# main.net
KiCad netlist of a schematic drawn in Altium Designer
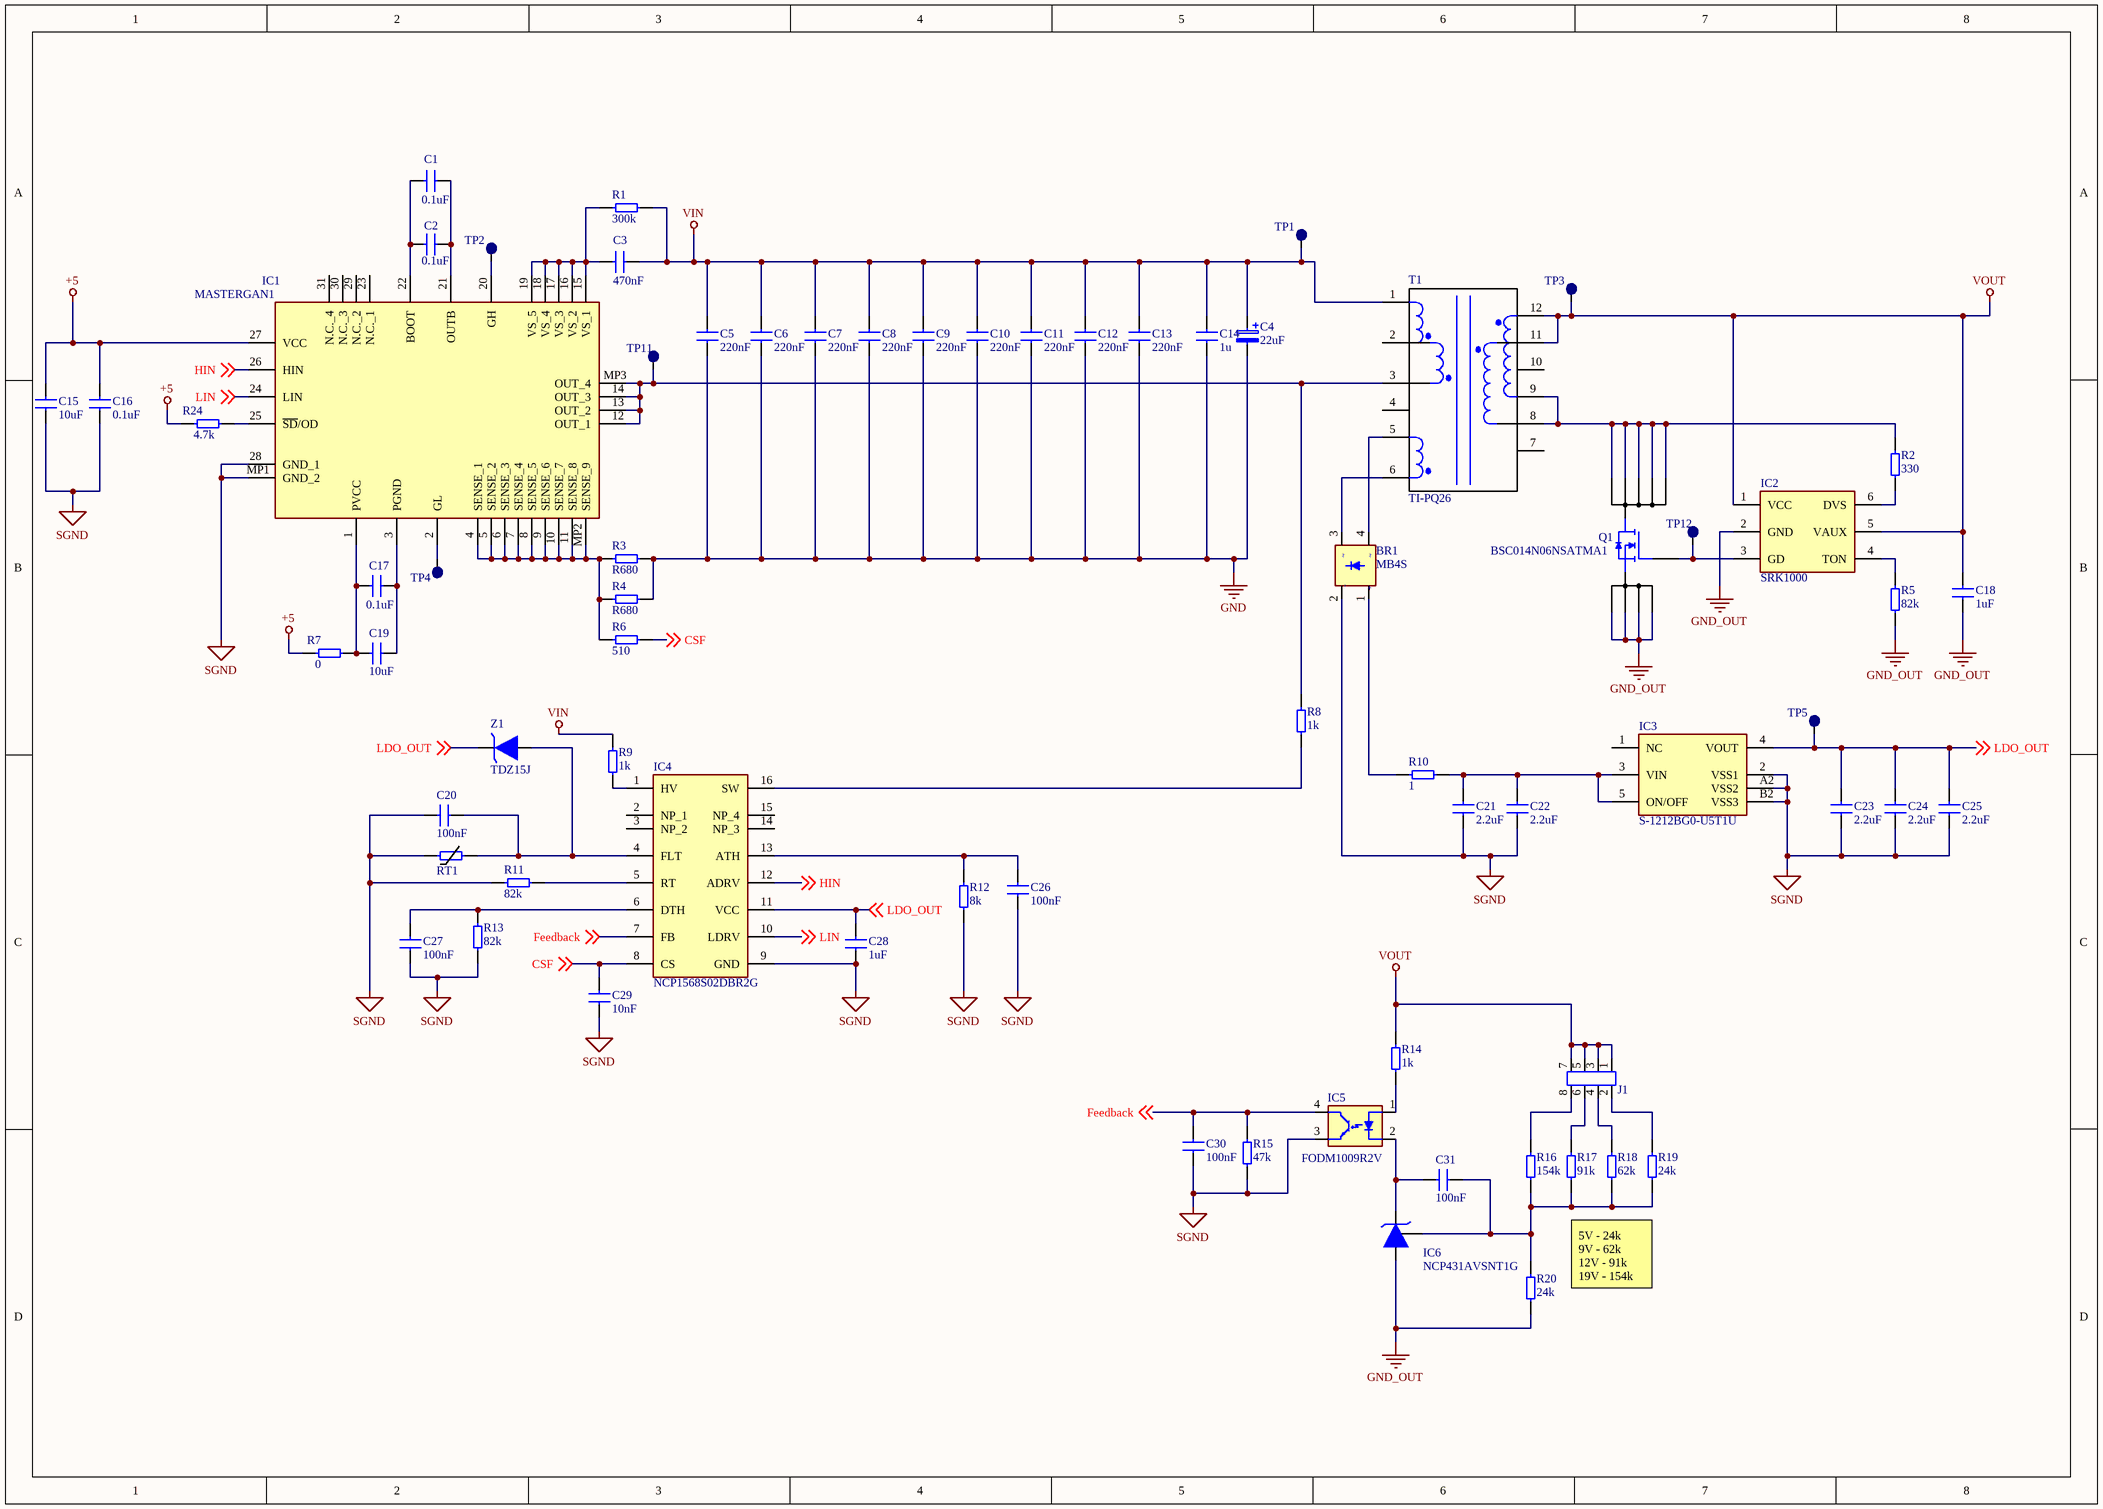
[diagram p0: main.SchDoc]

(export (version "E")
  (design (tool "Eeschema 10.0.6"))
  (components
    (comp (ref "BR1")
      (value "MB4S")
      (footprint "KN_ECART:SOP245P670X290-4N")
      (description "Bridge Rectifier")
      (fields (field (name "MOUSER PART NUMBER") "512-MB4S"))
      (libsource (lib "KN_ECART") (part "MB4S"))
    )
    (comp (ref "C1")
      (value "0.1uF")
      (footprint "KN_ECART:Capcitor_1206")
      (description "Capacitor - Standard SMD")
      (fields (field (name "VOLTAGE") "25V"))
      (libsource (lib "KN_ECART") (part "Capacitor_1206"))
    )
    (comp (ref "C2")
      (value "0.1uF")
      (footprint "KN_ECART:Capcitor_1206")
      (description "Capacitor - Standard SMD")
      (fields (field (name "VOLTAGE") "25V"))
      (libsource (lib "KN_ECART") (part "Capacitor_1206"))
    )
    (comp (ref "C3")
      (value "470nF")
      (footprint "KN_ECART:Capacitor_1812")
      (description "Capacitor - Standard SMD")
      (fields (field (name "VOLTAGE") "450V") (field (name "MPN") "CGA8N4X7T2W474K230KA"))
      (libsource (lib "") (part "Capacitor_1812_1"))
    )
    (comp (ref "C4")
      (value "22uF")
      (footprint "KN_ECART:CAPPRD500W60D1300H2700")
      (description "Capacitor - Electrolytic  THT")
      (fields (field (name "VOLTAGE") "500V") (field (name "MPN") "ESH226M500AL4AA"))
      (libsource (lib "KN_ECART") (part "Capacitor_Electrolytic_THT"))
    )
    (comp (ref "C5")
      (value "220nF")
      (footprint "KN_ECART:Capacitor_1812")
      (description "Capacitor - Standard SMD")
      (fields (field (name "VOLTAGE") "500") (field (name "MPN") "C1812C224MCRACTU"))
      (libsource (lib "") (part "Capacitor_1812_1"))
    )
    (comp (ref "C6")
      (value "220nF")
      (footprint "KN_ECART:Capacitor_1812")
      (description "Capacitor - Standard SMD")
      (fields (field (name "VOLTAGE") "500") (field (name "MPN") "C1812C224MCRACTU"))
      (libsource (lib "KN_ECART") (part "Capacitor_1812"))
    )
    (comp (ref "C7")
      (value "220nF")
      (footprint "KN_ECART:Capacitor_1812")
      (description "Capacitor - Standard SMD")
      (fields (field (name "VOLTAGE") "500") (field (name "MPN") "C1812C224MCRACTU"))
      (libsource (lib "") (part "Capacitor_1812_1"))
    )
    (comp (ref "C8")
      (value "220nF")
      (footprint "KN_ECART:Capacitor_1812")
      (description "Capacitor - Standard SMD")
      (fields (field (name "VOLTAGE") "500") (field (name "MPN") "C1812C224MCRACTU"))
      (libsource (lib "KN_ECART") (part "Capacitor_1812"))
    )
    (comp (ref "C9")
      (value "220nF")
      (footprint "KN_ECART:Capacitor_1812")
      (description "Capacitor - Standard SMD")
      (fields (field (name "VOLTAGE") "500") (field (name "MPN") "C1812C224MCRACTU"))
      (libsource (lib "") (part "Capacitor_1812_1"))
    )
    (comp (ref "C10")
      (value "220nF")
      (footprint "KN_ECART:Capacitor_1812")
      (description "Capacitor - Standard SMD")
      (fields (field (name "VOLTAGE") "500") (field (name "MPN") "C1812C224MCRACTU"))
      (libsource (lib "KN_ECART") (part "Capacitor_1812"))
    )
    (comp (ref "C11")
      (value "220nF")
      (footprint "KN_ECART:Capacitor_1812")
      (description "Capacitor - Standard SMD")
      (fields (field (name "VOLTAGE") "500") (field (name "MPN") "C1812C224MCRACTU"))
      (libsource (lib "KN_ECART") (part "Capacitor_1812"))
    )
    (comp (ref "C12")
      (value "220nF")
      (footprint "KN_ECART:Capacitor_1812")
      (description "Capacitor - Standard SMD")
      (fields (field (name "VOLTAGE") "500") (field (name "MPN") "C1812C224MCRACTU"))
      (libsource (lib "") (part "Capacitor_1812_1"))
    )
    (comp (ref "C13")
      (value "220nF")
      (footprint "KN_ECART:Capacitor_1812")
      (description "Capacitor - Standard SMD")
      (fields (field (name "VOLTAGE") "500") (field (name "MPN") "C1812C224MCRACTU"))
      (libsource (lib "KN_ECART") (part "Capacitor_1812"))
    )
    (comp (ref "C14")
      (value "1u")
      (footprint "TDKB58031")
      (description "Capacitor - Standard SMD")
      (fields (field (name "VOLTAGE") "450V") (field (name "MPN") "1206B104K451CT"))
      (libsource (lib "") (part "Capacitor_1206_2"))
    )
    (comp (ref "C15")
      (value "10uF")
      (footprint "KN_ECART:Capcitor_1206")
      (description "Capacitor - Standard SMD")
      (fields (field (name "VOLTAGE") "16V"))
      (libsource (lib "KN_ECART") (part "Capacitor_1206"))
    )
    (comp (ref "C16")
      (value "0.1uF")
      (footprint "KN_ECART:Capcitor_1206")
      (description "Capacitor - Standard SMD")
      (fields (field (name "VOLTAGE") "16V"))
      (libsource (lib "") (part "Capacitor_1206_1"))
    )
    (comp (ref "C17")
      (value "0.1uF")
      (footprint "KN_ECART:Capcitor_1206")
      (description "Capacitor - Standard SMD")
      (fields (field (name "VOLTAGE") "16V"))
      (libsource (lib "") (part "Capacitor_1206_1"))
    )
    (comp (ref "C18")
      (value "1uF")
      (footprint "KN_ECART:Capcitor_1206")
      (description "Capacitor - Standard SMD")
      (fields (field (name "VOLTAGE") "50") (field (name "MPN") "CL31B105KBHNFNE"))
      (libsource (lib "KN_ECART") (part "Capacitor_1206"))
    )
    (comp (ref "C19")
      (value "10uF")
      (footprint "KN_ECART:Capcitor_1206")
      (description "Capacitor - Standard SMD")
      (fields (field (name "VOLTAGE") "16V"))
      (libsource (lib "") (part "Capacitor_1206_1"))
    )
    (comp (ref "C20")
      (value "100nF")
      (footprint "KN_ECART:Capcitor_1206")
      (description "Capacitor - Standard SMD")
      (fields (field (name "VOLTAGE") "50V"))
      (libsource (lib "") (part "Capacitor_1206_1"))
    )
    (comp (ref "C21")
      (value "2.2uF")
      (footprint "KN_ECART:Capcitor_1206")
      (description "Capacitor - Standard SMD")
      (fields (field (name "VOLTAGE") "50V") (field (name "MPN") "CL31B225KBHNFNE"))
      (libsource (lib "") (part "Capacitor_1206_1"))
    )
    (comp (ref "C22")
      (value "2.2uF")
      (footprint "KN_ECART:Capcitor_1206")
      (description "Capacitor - Standard SMD")
      (fields (field (name "VOLTAGE") "50V") (field (name "MPN") "CL31B225KBHNFNE"))
      (libsource (lib "") (part "Capacitor_1206_1"))
    )
    (comp (ref "C23")
      (value "2.2uF")
      (footprint "KN_ECART:Capcitor_1206")
      (description "Capacitor - Standard SMD")
      (fields (field (name "VOLTAGE") "50V") (field (name "MPN") "CL31B225KBHNFNE"))
      (libsource (lib "") (part "Capacitor_1206_1"))
    )
    (comp (ref "C24")
      (value "2.2uF")
      (footprint "KN_ECART:Capcitor_1206")
      (description "Capacitor - Standard SMD")
      (fields (field (name "VOLTAGE") "50V") (field (name "MPN") "CL31B225KBHNFNE"))
      (libsource (lib "") (part "Capacitor_1206_1"))
    )
    (comp (ref "C25")
      (value "2.2uF")
      (footprint "KN_ECART:Capcitor_1206")
      (description "Capacitor - Standard SMD")
      (fields (field (name "VOLTAGE") "50V") (field (name "MPN") "CL31B225KBHNFNE"))
      (libsource (lib "") (part "Capacitor_1206_1"))
    )
    (comp (ref "C26")
      (value "100nF")
      (footprint "KN_ECART:Capcitor_1206")
      (description "Capacitor - Standard SMD")
      (fields (field (name "VOLTAGE") "50V"))
      (libsource (lib "") (part "Capacitor_1206_1"))
    )
    (comp (ref "C27")
      (value "100nF")
      (footprint "KN_ECART:Capcitor_1206")
      (description "Capacitor - Standard SMD")
      (fields (field (name "VOLTAGE") "50V"))
      (libsource (lib "KN_ECART") (part "Capacitor_1206"))
    )
    (comp (ref "C28")
      (value "1uF")
      (footprint "KN_ECART:Capacitor_0805")
      (description "Capacitor - Standard SMD")
      (fields (field (name "VOLTAGE") "25V"))
      (libsource (lib "KN_ECART") (part "Capacitor_0805"))
    )
    (comp (ref "C29")
      (value "10nF")
      (footprint "KN_ECART:Capcitor_1206")
      (description "Capacitor - Standard SMD")
      (fields (field (name "VOLTAGE") "50V"))
      (libsource (lib "KN_ECART") (part "Capacitor_1206"))
    )
    (comp (ref "C30")
      (value "100nF")
      (footprint "KN_ECART:Capcitor_1206")
      (description "Capacitor - Standard SMD")
      (fields (field (name "VOLTAGE") "50V"))
      (libsource (lib "") (part "Capacitor_1206_1"))
    )
    (comp (ref "C31")
      (value "100nF")
      (footprint "KN_ECART:Capcitor_1206")
      (description "Capacitor - Standard SMD")
      (fields (field (name "VOLTAGE") "50V"))
      (libsource (lib "KN_ECART") (part "Capacitor_1206"))
    )
    (comp (ref "IC1")
      (value "MASTERGAN1")
      (footprint "MASTERGAN1")
      (description "Integrated Circuit")
      (fields (field (name "MOUSER PART NUMBER") "511-MASTERGAN1"))
      (libsource (lib "KN_ECART") (part "MASTERGAN1"))
    )
    (comp (ref "IC2")
      (value "SRK1000")
      (footprint "KN_ECART:SOT95P280X145-6N")
      (description "Integrated Circuit")
      (fields (field (name "MOUSER PART NUMBER") "511-SRK1000"))
      (libsource (lib "KN_ECART") (part "SRK1000"))
    )
    (comp (ref "IC3")
      (value "S-1212BG0-U5T1U")
      (footprint "KN_ECART:S1212BG0U5T1U")
      (description "Integrated Circuit")
      (fields (field (name "MOUSER PART NUMBER") "628-S-1212BG0-U5T1U"))
      (libsource (lib "KN_ECART") (part "S-1212BG0-U5T1U"))
    )
    (comp (ref "IC4")
      (value "NCP1568S02DBR2G")
      (footprint "KN_ECART:SOIC127P600X175-16N")
      (description "Integrated Circuit")
      (fields (field (name "MOUSER PART NUMBER") "863-NCP1568S02DBR2G"))
      (libsource (lib "KN_ECART") (part "NCP1568S02DBR2G"))
    )
    (comp (ref "IC5")
      (value "FODM1009R2V")
      (footprint "KN_ECART:FODM1009R2V")
      (description "Integrated Circuit")
      (fields (field (name "MOUSER PART NUMBER") "863-FODM1009R2V"))
      (libsource (lib "KN_ECART") (part "FODM1009R2V"))
    )
    (comp (ref "IC6")
      (value "NCP431AVSNT1G")
      (footprint "SOT96P237X111-3N")
      (description "Programmable Precision\r\nReference")
      (fields (field (name "MOUSER PART NUMBER") "863-NCP431AVSNT1G"))
      (libsource (lib "KN_ECART") (part "NCP431AVSNT1G"))
    )
    (comp (ref "J1")
      (value "Header_2x4")
      (footprint "Header_2x4")
      (libsource (lib "KN_ECART") (part "Header_2x4"))
    )
    (comp (ref "Q1")
      (value "BSC014N06NSATMA1")
      (footprint "BSC010N04LS6ATMA1")
      (description "MOSFET (N-Channel)")
      (fields (field (name "MOUSER PART NUMBER") "726-BSC014N06NSATMA1"))
      (libsource (lib "KN_ECART") (part "BSC014N06NSATMA1"))
    )
    (comp (ref "R1")
      (value "300k")
      (footprint "KN_ECART:Resistor_1206")
      (description "Resistor - Standard SMD")
      (libsource (lib "KN_ECART") (part "Resistor_1206"))
    )
    (comp (ref "R2")
      (value "330")
      (footprint "KN_ECART:Resistor_1206")
      (description "Resistor - Standard SMD")
      (libsource (lib "KN_ECART") (part "Resistor_1206"))
    )
    (comp (ref "R3")
      (value "R680")
      (footprint "KN_ECART:Resistor_1206")
      (description "Resistor - Standard SMD")
      (fields (field (name "MPN") "PE1206FRF7W0R68L"))
      (libsource (lib "KN_ECART") (part "Resistor_1206"))
    )
    (comp (ref "R4")
      (value "R680")
      (footprint "KN_ECART:Resistor_1206")
      (description "Resistor - Standard SMD")
      (fields (field (name "MPN") "PE1206FRF7W0R68L"))
      (libsource (lib "KN_ECART") (part "Resistor_1206"))
    )
    (comp (ref "R5")
      (value "82k")
      (footprint "KN_ECART:Resistor_1206")
      (description "Resistor - Standard SMD")
      (libsource (lib "KN_ECART") (part "Resistor_1206"))
    )
    (comp (ref "R6")
      (value "510")
      (footprint "KN_ECART:Resistor_1206")
      (description "Resistor - Standard SMD")
      (libsource (lib "KN_ECART") (part "Resistor_1206"))
    )
    (comp (ref "R7")
      (value "0")
      (footprint "KN_ECART:Resistor_0805")
      (description "Resistor - Standard SMD")
      (libsource (lib "KN_ECART") (part "Resistor_0805"))
    )
    (comp (ref "R8")
      (value "1k")
      (footprint "KN_ECART:Resistor_1206")
      (description "Resistor - Standard SMD")
      (libsource (lib "KN_ECART") (part "Resistor_1206"))
    )
    (comp (ref "R9")
      (value "1k")
      (footprint "KN_ECART:Resistor_1206")
      (description "Resistor - Standard SMD")
      (libsource (lib "KN_ECART") (part "Resistor_1206"))
    )
    (comp (ref "R10")
      (value "1")
      (footprint "KN_ECART:Resistor_1206")
      (description "Resistor - Standard SMD")
      (libsource (lib "KN_ECART") (part "Resistor_1206"))
    )
    (comp (ref "R11")
      (value "82k")
      (footprint "KN_ECART:Resistor_1206")
      (description "Resistor - Standard SMD")
      (libsource (lib "KN_ECART") (part "Resistor_1206"))
    )
    (comp (ref "R12")
      (value "8k")
      (footprint "KN_ECART:Resistor_1206")
      (description "Resistor - Standard SMD")
      (libsource (lib "KN_ECART") (part "Resistor_1206"))
    )
    (comp (ref "R13")
      (value "82k")
      (footprint "KN_ECART:Resistor_1206")
      (description "Resistor - Standard SMD")
      (libsource (lib "KN_ECART") (part "Resistor_1206"))
    )
    (comp (ref "R14")
      (value "1k")
      (footprint "KN_ECART:Resistor_1206")
      (description "Resistor - Standard SMD")
      (libsource (lib "KN_ECART") (part "Resistor_1206"))
    )
    (comp (ref "R15")
      (value "47k")
      (footprint "KN_ECART:Resistor_1206")
      (description "Resistor - Standard SMD")
      (libsource (lib "KN_ECART") (part "Resistor_1206"))
    )
    (comp (ref "R16")
      (value "154k")
      (footprint "KN_ECART:Resistor_0805")
      (description "Resistor - Standard SMD")
      (libsource (lib "KN_ECART") (part "Resistor_0805"))
    )
    (comp (ref "R17")
      (value "91k")
      (footprint "KN_ECART:Resistor_0805")
      (description "Resistor - Standard SMD")
      (libsource (lib "KN_ECART") (part "Resistor_0805"))
    )
    (comp (ref "R18")
      (value "62k")
      (footprint "KN_ECART:Resistor_0805")
      (description "Resistor - Standard SMD")
      (libsource (lib "KN_ECART") (part "Resistor_0805"))
    )
    (comp (ref "R19")
      (value "24k")
      (footprint "KN_ECART:Resistor_0805")
      (description "Resistor - Standard SMD")
      (libsource (lib "KN_ECART") (part "Resistor_0805"))
    )
    (comp (ref "R20")
      (value "24k")
      (footprint "KN_ECART:Resistor_1206")
      (description "Resistor - Standard SMD")
      (libsource (lib "KN_ECART") (part "Resistor_1206"))
    )
    (comp (ref "R24")
      (value "4.7k")
      (footprint "KN_ECART:Resistor_0805")
      (description "Resistor - Standard SMD")
      (libsource (lib "KN_ECART") (part "Resistor_0805"))
    )
    (comp (ref "RT1")
      (value "NTCG104EF104FT1SX")
      (footprint "KN_ECART:THRMC1005X55N")
      (description "Thermistor")
      (fields (field (name "MOUSER PART NUMBER") "810-NTC104EF104FT1SX"))
      (libsource (lib "KN_ECART") (part "NTCG104EF104FT1SX"))
    )
    (comp (ref "T1")
      (value "TI-PQ26")
      (footprint "PQ26-20-K")
      (description "Transformer")
      (fields (field (name "MPN") "TI-PQ26/20-EPR11"))
      (libsource (lib "KN_ECART") (part "TI-PQ26"))
    )
    (comp (ref "TP1")
      (value "Test point")
      (footprint "Test point")
      (libsource (lib "KN_ECART") (part "Test point"))
    )
    (comp (ref "TP2")
      (value "Test point")
      (footprint "Test point")
      (libsource (lib "KN_ECART") (part "Test point"))
    )
    (comp (ref "TP3")
      (value "Test point")
      (footprint "Test point")
      (libsource (lib "KN_ECART") (part "Test point"))
    )
    (comp (ref "TP4")
      (value "Test point")
      (footprint "Test point")
      (libsource (lib "KN_ECART") (part "Test point"))
    )
    (comp (ref "TP5")
      (value "Test point")
      (footprint "Test point")
      (libsource (lib "KN_ECART") (part "Test point"))
    )
    (comp (ref "TP11")
      (value "Test point")
      (footprint "Test point")
      (libsource (lib "KN_ECART") (part "Test point"))
    )
    (comp (ref "TP12")
      (value "Test point")
      (footprint "Test point")
      (libsource (lib "KN_ECART") (part "Test point"))
    )
    (comp (ref "Z1")
      (value "TDZ15J")
      (footprint "KN_ECART:SODFL4725X105N")
      (description "Zener Diode")
      (fields (field (name "ARROW PART NUMBER") "TDZ3V3J,115"))
      (libsource (lib "KN_ECART") (part "TDZ15J"))
    )
  )
  (nets
    (net (code "1") (name "+5") (class "Default")
      (node (ref "C15") (pin "2") (pintype "passive"))
      (node (ref "C16") (pin "1") (pintype "passive"))
      (node (ref "IC1") (pin "27") (pinfunction "VCC_27") (pintype "passive"))
      (node (ref "R24") (pin "1") (pintype "passive"))
      (node (ref "R7") (pin "1") (pintype "passive"))
    )
    (net (code "2") (name "CSF") (class "Default")
      (node (ref "C29") (pin "1") (pintype "passive"))
      (node (ref "IC4") (pin "8") (pinfunction "CS_8") (pintype "passive"))
      (node (ref "R6") (pin "1") (pintype "passive"))
    )
    (net (code "3") (name "Feedback") (class "Default")
      (node (ref "C30") (pin "2") (pintype "passive"))
      (node (ref "IC4") (pin "7") (pinfunction "FB_7") (pintype "passive"))
      (node (ref "IC5") (pin "4") (pinfunction "C_4") (pintype "passive"))
      (node (ref "R15") (pin "2") (pintype "passive"))
    )
    (net (code "4") (name "GND") (class "Default")
      (node (ref "C10") (pin "2") (pintype "passive"))
      (node (ref "C11") (pin "2") (pintype "passive"))
      (node (ref "C12") (pin "1") (pintype "passive"))
      (node (ref "C13") (pin "2") (pintype "passive"))
      (node (ref "C14") (pin "2") (pintype "passive"))
      (node (ref "C4") (pin "2") (pintype "passive"))
      (node (ref "C5") (pin "1") (pintype "passive"))
      (node (ref "C6") (pin "2") (pintype "passive"))
      (node (ref "C7") (pin "1") (pintype "passive"))
      (node (ref "C8") (pin "2") (pintype "passive"))
      (node (ref "C9") (pin "1") (pintype "passive"))
      (node (ref "R3") (pin "2") (pintype "passive"))
      (node (ref "R4") (pin "2") (pintype "passive"))
    )
    (net (code "5") (name "GND_OUT") (class "Default")
      (node (ref "C18") (pin "1") (pintype "passive"))
      (node (ref "IC2") (pin "2") (pinfunction "GND_2") (pintype "passive"))
      (node (ref "IC6") (pin "3") (pinfunction "A_3") (pintype "passive"))
      (node (ref "Q1") (pin "1") (pinfunction "S_1_1") (pintype "passive"))
      (node (ref "Q1") (pin "10") (pinfunction "S_4_10") (pintype "passive"))
      (node (ref "Q1") (pin "2") (pinfunction "S_2_2") (pintype "passive"))
      (node (ref "Q1") (pin "3") (pinfunction "S_3_3") (pintype "passive"))
      (node (ref "R20") (pin "1") (pintype "passive"))
      (node (ref "R5") (pin "1") (pintype "passive"))
    )
    (net (code "6") (name "HIN") (class "Default")
      (node (ref "IC1") (pin "26") (pinfunction "HIN_26") (pintype "passive"))
      (node (ref "IC4") (pin "12") (pinfunction "ADRV_12") (pintype "passive"))
    )
    (net (code "7") (name "LDO_OUT") (class "Default")
      (node (ref "C23") (pin "2") (pintype "passive"))
      (node (ref "C24") (pin "2") (pintype "passive"))
      (node (ref "C25") (pin "2") (pintype "passive"))
      (node (ref "C28") (pin "2") (pintype "passive"))
      (node (ref "IC3") (pin "4") (pinfunction "VOUT_4") (pintype "passive"))
      (node (ref "IC4") (pin "11") (pinfunction "VCC_11") (pintype "passive"))
      (node (ref "TP5") (pin "1") (pintype "passive"))
      (node (ref "Z1") (pin "1") (pinfunction "K_1") (pintype "passive"))
    )
    (net (code "8") (name "LIN") (class "Default")
      (node (ref "IC1") (pin "24") (pinfunction "LIN_24") (pintype "passive"))
      (node (ref "IC4") (pin "10") (pinfunction "LDRV_10") (pintype "passive"))
    )
    (net (code "9") (name "Net-(BR1-Pad1)") (class "Default")
      (node (ref "BR1") (pin "1") (pintype "passive"))
      (node (ref "R10") (pin "1") (pintype "passive"))
    )
    (net (code "10") (name "Net-(BR1-Pad3)") (class "Default")
      (node (ref "BR1") (pin "3") (pintype "passive"))
      (node (ref "T1") (pin "6") (pintype "passive"))
    )
    (net (code "11") (name "Net-(BR1-Pad4)") (class "Default")
      (node (ref "BR1") (pin "4") (pintype "passive"))
      (node (ref "T1") (pin "5") (pintype "passive"))
    )
    (net (code "12") (name "Net-(IC1-BOOT)") (class "Default")
      (node (ref "C1") (pin "1") (pintype "passive"))
      (node (ref "C2") (pin "1") (pintype "passive"))
      (node (ref "IC1") (pin "22") (pinfunction "BOOT_22") (pintype "passive"))
    )
    (net (code "13") (name "Net-(IC1-GH)") (class "Default")
      (node (ref "IC1") (pin "20") (pinfunction "GH_20") (pintype "passive"))
      (node (ref "TP2") (pin "1") (pintype "passive"))
    )
    (net (code "14") (name "Net-(IC1-GL)") (class "Default")
      (node (ref "IC1") (pin "2") (pinfunction "GL_2") (pintype "passive"))
      (node (ref "TP4") (pin "1") (pintype "passive"))
    )
    (net (code "15") (name "Net-(IC1-OUTB)") (class "Default")
      (node (ref "C1") (pin "2") (pintype "passive"))
      (node (ref "C2") (pin "2") (pintype "passive"))
      (node (ref "IC1") (pin "21") (pinfunction "OUTB_21") (pintype "passive"))
    )
    (net (code "16") (name "Net-(IC1-OUT_1)") (class "Default")
      (node (ref "IC1") (pin "12") (pinfunction "OUT_1_12") (pintype "passive"))
      (node (ref "IC1") (pin "13") (pinfunction "OUT_2_13") (pintype "passive"))
      (node (ref "IC1") (pin "14") (pinfunction "OUT_3_14") (pintype "passive"))
      (node (ref "IC1") (pin "MP3") (pinfunction "OUT_4_MP3") (pintype "passive"))
      (node (ref "R8") (pin "2") (pintype "passive"))
      (node (ref "T1") (pin "3") (pintype "passive"))
      (node (ref "TP11") (pin "1") (pintype "passive"))
    )
    (net (code "17") (name "Net-(IC1-PGND)") (class "Default")
      (node (ref "C17") (pin "2") (pintype "passive"))
      (node (ref "C19") (pin "2") (pintype "passive"))
      (node (ref "IC1") (pin "3") (pinfunction "PGND_3") (pintype "passive"))
    )
    (net (code "18") (name "Net-(IC1-PVCC)") (class "Default")
      (node (ref "C17") (pin "1") (pintype "passive"))
      (node (ref "C19") (pin "1") (pintype "passive"))
      (node (ref "IC1") (pin "1") (pinfunction "PVCC_1") (pintype "passive"))
      (node (ref "R7") (pin "2") (pintype "passive"))
    )
    (net (code "19") (name "Net-(IC1-SENSE_1)") (class "Default")
      (node (ref "IC1") (pin "10") (pinfunction "SENSE_7_10") (pintype "passive"))
      (node (ref "IC1") (pin "11") (pinfunction "SENSE_8_11") (pintype "passive"))
      (node (ref "IC1") (pin "4") (pinfunction "SENSE_1_4") (pintype "passive"))
      (node (ref "IC1") (pin "5") (pinfunction "SENSE_2_5") (pintype "passive"))
      (node (ref "IC1") (pin "6") (pinfunction "SENSE_3_6") (pintype "passive"))
      (node (ref "IC1") (pin "7") (pinfunction "SENSE_4_7") (pintype "passive"))
      (node (ref "IC1") (pin "8") (pinfunction "SENSE_5_8") (pintype "passive"))
      (node (ref "IC1") (pin "9") (pinfunction "SENSE_6_9") (pintype "passive"))
      (node (ref "IC1") (pin "MP2") (pinfunction "SENSE_9_MP2") (pintype "passive"))
      (node (ref "R3") (pin "1") (pintype "passive"))
      (node (ref "R4") (pin "1") (pintype "passive"))
      (node (ref "R6") (pin "2") (pintype "passive"))
    )
    (net (code "20") (name "Net-(IC1-VS_1)") (class "Default")
      (node (ref "C3") (pin "1") (pintype "passive"))
      (node (ref "IC1") (pin "15") (pinfunction "VS_1_15") (pintype "passive"))
      (node (ref "IC1") (pin "16") (pinfunction "VS_2_16") (pintype "passive"))
      (node (ref "IC1") (pin "17") (pinfunction "VS_3_17") (pintype "passive"))
      (node (ref "IC1") (pin "18") (pinfunction "VS_4_18") (pintype "passive"))
      (node (ref "IC1") (pin "19") (pinfunction "VS_5_19") (pintype "passive"))
      (node (ref "R1") (pin "1") (pintype "passive"))
    )
    (net (code "21") (name "Net-(IC1-~{SD}{slash}OD)") (class "Default")
      (node (ref "IC1") (pin "25") (pinfunction "~{SD}/OD_25") (pintype "passive"))
      (node (ref "R24") (pin "2") (pintype "passive"))
    )
    (net (code "22") (name "Net-(IC2-DVS)") (class "Default")
      (node (ref "IC2") (pin "6") (pinfunction "DVS_6") (pintype "passive"))
      (node (ref "R2") (pin "1") (pintype "passive"))
    )
    (net (code "23") (name "Net-(IC2-GD)") (class "Default")
      (node (ref "IC2") (pin "3") (pinfunction "GD_3") (pintype "passive"))
      (node (ref "Q1") (pin "4") (pinfunction "G_4") (pintype "passive"))
      (node (ref "TP12") (pin "1") (pintype "passive"))
    )
    (net (code "24") (name "Net-(IC2-TON)") (class "Default")
      (node (ref "IC2") (pin "4") (pinfunction "TON_4") (pintype "passive"))
      (node (ref "R5") (pin "2") (pintype "passive"))
    )
    (net (code "25") (name "Net-(IC3-ON{slash}OFF)") (class "Default")
      (node (ref "C21") (pin "2") (pintype "passive"))
      (node (ref "C22") (pin "2") (pintype "passive"))
      (node (ref "IC3") (pin "3") (pinfunction "VIN_3") (pintype "passive"))
      (node (ref "IC3") (pin "5") (pinfunction "ON/OFF_5") (pintype "passive"))
      (node (ref "R10") (pin "2") (pintype "passive"))
    )
    (net (code "26") (name "Net-(IC4-ATH)") (class "Default")
      (node (ref "C26") (pin "2") (pintype "passive"))
      (node (ref "IC4") (pin "13") (pinfunction "ATH_13") (pintype "passive"))
      (node (ref "R12") (pin "2") (pintype "passive"))
    )
    (net (code "27") (name "Net-(IC4-DTH)") (class "Default")
      (node (ref "C27") (pin "1") (pintype "passive"))
      (node (ref "IC4") (pin "6") (pinfunction "DTH_6") (pintype "passive"))
      (node (ref "R13") (pin "1") (pintype "passive"))
    )
    (net (code "28") (name "Net-(IC4-FLT)") (class "Default")
      (node (ref "C20") (pin "2") (pintype "passive"))
      (node (ref "IC4") (pin "4") (pinfunction "FLT_4") (pintype "passive"))
      (node (ref "RT1") (pin "2") (pintype "passive"))
      (node (ref "Z1") (pin "2") (pinfunction "A_2") (pintype "passive"))
    )
    (net (code "29") (name "Net-(IC4-HV)") (class "Default")
      (node (ref "IC4") (pin "1") (pinfunction "HV_1") (pintype "passive"))
      (node (ref "R9") (pin "1") (pintype "passive"))
    )
    (net (code "30") (name "Net-(IC4-RT)") (class "Default")
      (node (ref "IC4") (pin "5") (pinfunction "RT_5") (pintype "passive"))
      (node (ref "R11") (pin "1") (pintype "passive"))
    )
    (net (code "31") (name "Net-(IC4-SW)") (class "Default")
      (node (ref "IC4") (pin "16") (pinfunction "SW_16") (pintype "passive"))
      (node (ref "R8") (pin "1") (pintype "passive"))
    )
    (net (code "32") (name "Net-(IC5-A)") (class "Default")
      (node (ref "IC5") (pin "1") (pinfunction "A_1") (pintype "passive"))
      (node (ref "R14") (pin "1") (pintype "passive"))
    )
    (net (code "33") (name "Net-(IC5-K)") (class "Default")
      (node (ref "C31") (pin "1") (pintype "passive"))
      (node (ref "IC5") (pin "2") (pinfunction "K_2") (pintype "passive"))
      (node (ref "IC6") (pin "2") (pinfunction "K_2") (pintype "passive"))
    )
    (net (code "34") (name "Net-(IC6-REF)") (class "Default")
      (node (ref "C31") (pin "2") (pintype "passive"))
      (node (ref "IC6") (pin "1") (pinfunction "REF_1") (pintype "passive"))
      (node (ref "R16") (pin "1") (pintype "passive"))
      (node (ref "R17") (pin "1") (pintype "passive"))
      (node (ref "R18") (pin "1") (pintype "passive"))
      (node (ref "R19") (pin "1") (pintype "passive"))
      (node (ref "R20") (pin "2") (pintype "passive"))
    )
    (net (code "35") (name "Net-(J1-Pad2)") (class "Default")
      (node (ref "J1") (pin "2") (pinfunction "2_2") (pintype "passive"))
      (node (ref "R19") (pin "2") (pintype "passive"))
    )
    (net (code "36") (name "Net-(J1-Pad4)") (class "Default")
      (node (ref "J1") (pin "4") (pinfunction "4_4") (pintype "passive"))
      (node (ref "R18") (pin "2") (pintype "passive"))
    )
    (net (code "37") (name "Net-(J1-Pad6)") (class "Default")
      (node (ref "J1") (pin "6") (pinfunction "6_6") (pintype "passive"))
      (node (ref "R17") (pin "2") (pintype "passive"))
    )
    (net (code "38") (name "Net-(J1-Pad8)") (class "Default")
      (node (ref "J1") (pin "8") (pinfunction "8_8") (pintype "passive"))
      (node (ref "R16") (pin "2") (pintype "passive"))
    )
    (net (code "39") (name "Net-(Q1-D_1)") (class "Default")
      (node (ref "Q1") (pin "5") (pinfunction "D_1_5") (pintype "passive"))
      (node (ref "Q1") (pin "6") (pinfunction "D_2_6") (pintype "passive"))
      (node (ref "Q1") (pin "7") (pinfunction "D_3_7") (pintype "passive"))
      (node (ref "Q1") (pin "8") (pinfunction "D_4_8") (pintype "passive"))
      (node (ref "Q1") (pin "9") (pinfunction "D_5_9") (pintype "passive"))
      (node (ref "R2") (pin "2") (pintype "passive"))
      (node (ref "T1") (pin "8") (pintype "passive"))
      (node (ref "T1") (pin "9") (pintype "passive"))
    )
    (net (code "40") (name "SGND") (class "Default")
      (node (ref "BR1") (pin "2") (pintype "passive"))
      (node (ref "C15") (pin "1") (pintype "passive"))
      (node (ref "C16") (pin "2") (pintype "passive"))
      (node (ref "C20") (pin "1") (pintype "passive"))
      (node (ref "C21") (pin "1") (pintype "passive"))
      (node (ref "C22") (pin "1") (pintype "passive"))
      (node (ref "C23") (pin "1") (pintype "passive"))
      (node (ref "C24") (pin "1") (pintype "passive"))
      (node (ref "C25") (pin "1") (pintype "passive"))
      (node (ref "C26") (pin "1") (pintype "passive"))
      (node (ref "C27") (pin "2") (pintype "passive"))
      (node (ref "C28") (pin "1") (pintype "passive"))
      (node (ref "C29") (pin "2") (pintype "passive"))
      (node (ref "C30") (pin "1") (pintype "passive"))
      (node (ref "IC1") (pin "28") (pinfunction "GND_1_28") (pintype "passive"))
      (node (ref "IC1") (pin "MP1") (pinfunction "GND_2_MP1") (pintype "passive"))
      (node (ref "IC3") (pin "2") (pinfunction "VSS1_2") (pintype "passive"))
      (node (ref "IC3") (pin "A2") (pinfunction "VSS2_A2") (pintype "passive"))
      (node (ref "IC3") (pin "B2") (pinfunction "VSS3_B2") (pintype "passive"))
      (node (ref "IC4") (pin "9") (pinfunction "GND_9") (pintype "passive"))
      (node (ref "IC5") (pin "3") (pinfunction "E_3") (pintype "passive"))
      (node (ref "R11") (pin "2") (pintype "passive"))
      (node (ref "R12") (pin "1") (pintype "passive"))
      (node (ref "R13") (pin "2") (pintype "passive"))
      (node (ref "R15") (pin "1") (pintype "passive"))
      (node (ref "RT1") (pin "1") (pintype "passive"))
    )
    (net (code "41") (name "VIN") (class "Default")
      (node (ref "C10") (pin "1") (pintype "passive"))
      (node (ref "C11") (pin "1") (pintype "passive"))
      (node (ref "C12") (pin "2") (pintype "passive"))
      (node (ref "C13") (pin "1") (pintype "passive"))
      (node (ref "C14") (pin "1") (pintype "passive"))
      (node (ref "C3") (pin "2") (pintype "passive"))
      (node (ref "C4") (pin "1") (pintype "passive"))
      (node (ref "C5") (pin "2") (pintype "passive"))
      (node (ref "C6") (pin "1") (pintype "passive"))
      (node (ref "C7") (pin "2") (pintype "passive"))
      (node (ref "C8") (pin "1") (pintype "passive"))
      (node (ref "C9") (pin "2") (pintype "passive"))
      (node (ref "R1") (pin "2") (pintype "passive"))
      (node (ref "R9") (pin "2") (pintype "passive"))
      (node (ref "T1") (pin "1") (pintype "passive"))
      (node (ref "TP1") (pin "1") (pintype "passive"))
    )
    (net (code "42") (name "VOUT") (class "Default")
      (node (ref "C18") (pin "2") (pintype "passive"))
      (node (ref "IC2") (pin "1") (pinfunction "VCC_1") (pintype "passive"))
      (node (ref "IC2") (pin "5") (pinfunction "VAUX_5") (pintype "passive"))
      (node (ref "J1") (pin "1") (pintype "passive"))
      (node (ref "J1") (pin "3") (pinfunction "3_3") (pintype "passive"))
      (node (ref "J1") (pin "5") (pinfunction "5_5") (pintype "passive"))
      (node (ref "J1") (pin "7") (pinfunction "7_7") (pintype "passive"))
      (node (ref "R14") (pin "2") (pintype "passive"))
      (node (ref "T1") (pin "11") (pintype "passive"))
      (node (ref "T1") (pin "12") (pintype "passive"))
      (node (ref "TP3") (pin "1") (pintype "passive"))
    )
    (net (code "43") (name "unconnected-(IC1-N.C._1-Pad23)") (class "Default")
      (node (ref "IC1") (pin "23") (pinfunction "N.C._1_23") (pintype "passive"))
    )
    (net (code "44") (name "unconnected-(IC1-N.C._2-Pad29)") (class "Default")
      (node (ref "IC1") (pin "29") (pinfunction "N.C._2_29") (pintype "passive"))
    )
    (net (code "45") (name "unconnected-(IC1-N.C._3-Pad30)") (class "Default")
      (node (ref "IC1") (pin "30") (pinfunction "N.C._3_30") (pintype "passive"))
    )
    (net (code "46") (name "unconnected-(IC1-N.C._4-Pad31)") (class "Default")
      (node (ref "IC1") (pin "31") (pinfunction "N.C._4_31") (pintype "passive"))
    )
    (net (code "47") (name "unconnected-(IC3-NC-Pad1)") (class "Default")
      (node (ref "IC3") (pin "1") (pinfunction "NC_1") (pintype "passive"))
    )
    (net (code "48") (name "unconnected-(IC4-NP_1-Pad2)") (class "Default")
      (node (ref "IC4") (pin "2") (pinfunction "NP_1_2") (pintype "passive"))
    )
    (net (code "49") (name "unconnected-(IC4-NP_2-Pad3)") (class "Default")
      (node (ref "IC4") (pin "3") (pinfunction "NP_2_3") (pintype "passive"))
    )
    (net (code "50") (name "unconnected-(IC4-NP_3-Pad14)") (class "Default")
      (node (ref "IC4") (pin "14") (pinfunction "NP_3_14") (pintype "passive"))
    )
    (net (code "51") (name "unconnected-(IC4-NP_4-Pad15)") (class "Default")
      (node (ref "IC4") (pin "15") (pinfunction "NP_4_15") (pintype "passive"))
    )
    (net (code "52") (name "unconnected-(T1-Pad2)") (class "Default")
      (node (ref "T1") (pin "2") (pintype "passive"))
    )
    (net (code "53") (name "unconnected-(T1-Pad4)") (class "Default")
      (node (ref "T1") (pin "4") (pintype "passive"))
    )
    (net (code "54") (name "unconnected-(T1-Pad7)") (class "Default")
      (node (ref "T1") (pin "7") (pintype "passive"))
    )
    (net (code "55") (name "unconnected-(T1-Pad10)") (class "Default")
      (node (ref "T1") (pin "10") (pintype "passive"))
    )
  )
)
